# Sensors.net
KiCad netlist of a schematic drawn in Altium Designer
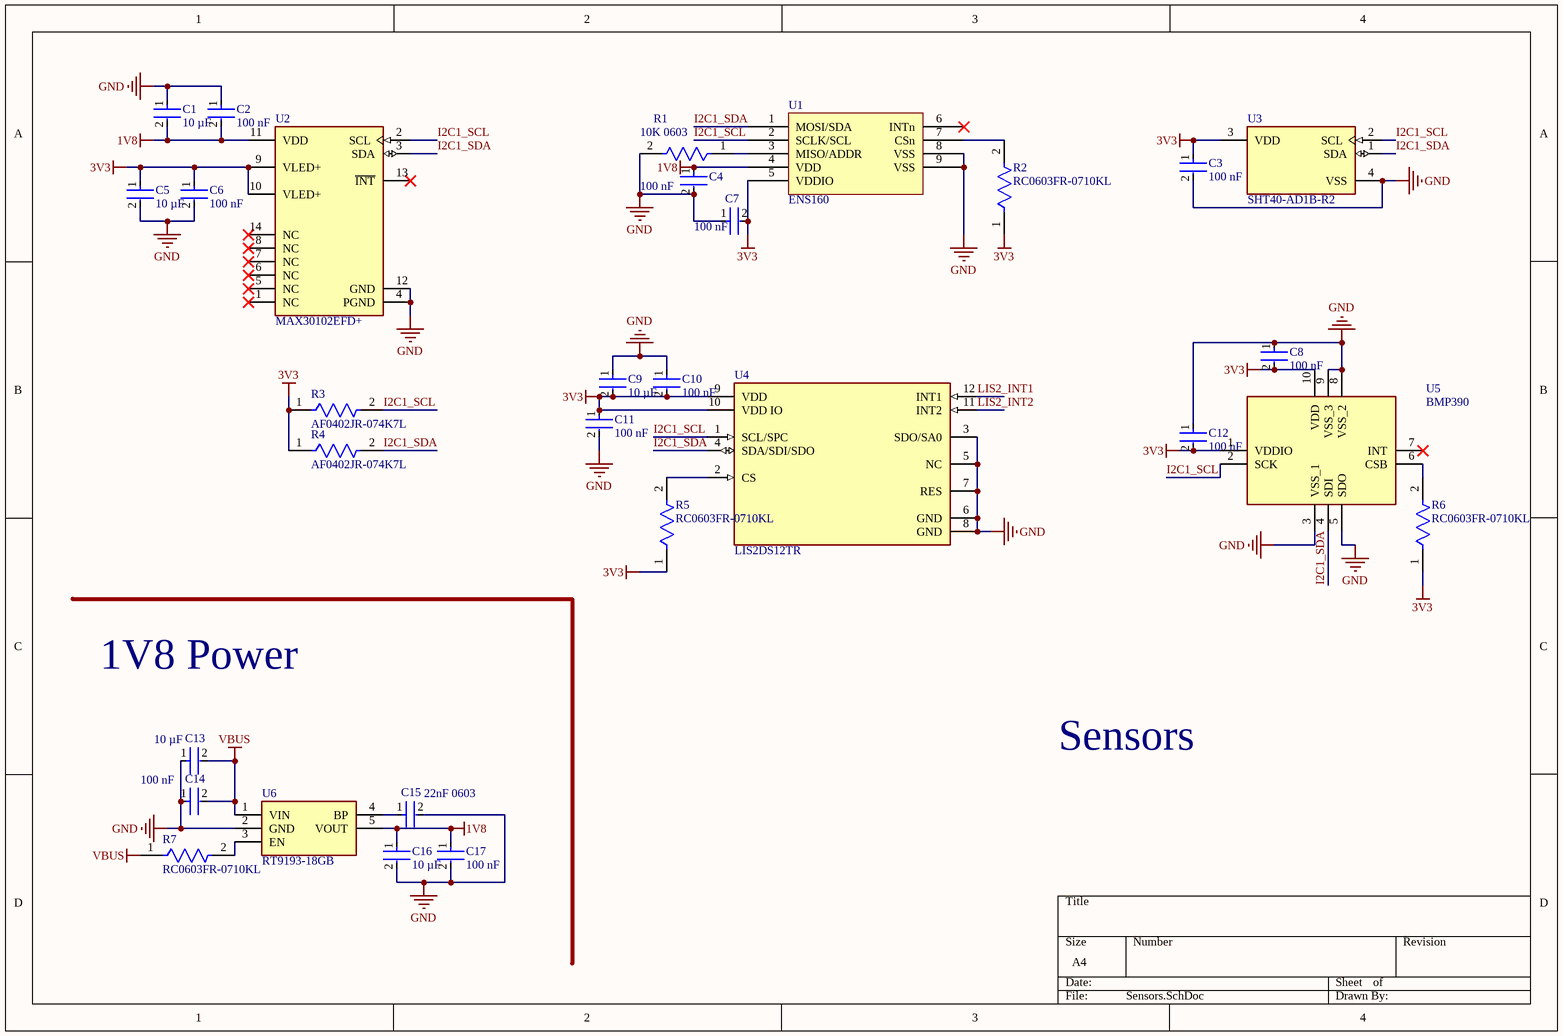
[diagram p0: Sensors.SchDoc]

(export (version "E")
  (design (tool "Eeschema 10.0.6"))
  (components
    (comp (ref "C1")
      (value "10 µF")
      (footprint "FP-CL10-IPC_C")
      (description "Cap Ceramic 10uF 25V X5R ±20% Pad SMD 0603 +85°C T/R")
      (fields (field (name "TOLERANCE") "20%"))
      (libsource (lib "Altium Content Vault") (part "b4654b650e69147ec39a6b967a45e02"))
    )
    (comp (ref "C2")
      (value "100 nF")
      (footprint "FP-CL10-IPC_A")
      (description "Cap Ceramic 100nF 100V X7R ±10% Pad SMD 0603 +125°C T/R")
      (fields (field (name "TOLERANCE") "10%"))
      (libsource (lib "Altium Content Vault") (part "b4654b650e69147ec39a6b967a45e02"))
    )
    (comp (ref "C3")
      (value "100 nF")
      (footprint "FP-CL10-IPC_A")
      (description "Cap Ceramic 100nF 100V X7R ±10% Pad SMD 0603 +125°C T/R")
      (fields (field (name "TOLERANCE") "10%"))
      (libsource (lib "Altium Content Vault") (part "b4654b650e69147ec39a6b967a45e02"))
    )
    (comp (ref "C4")
      (value "100 nF")
      (footprint "FP-CL10-IPC_A")
      (description "Cap Ceramic 100nF 100V X7R ±10% Pad SMD 0603 +125°C T/R")
      (fields (field (name "TOLERANCE") "10%"))
      (libsource (lib "Altium Content Vault") (part "b4654b650e69147ec39a6b967a45e02"))
    )
    (comp (ref "C5")
      (value "10 µF")
      (footprint "FP-CL10-IPC_C")
      (description "Cap Ceramic 10uF 25V X5R ±20% Pad SMD 0603 +85°C T/R")
      (fields (field (name "TOLERANCE") "20%"))
      (libsource (lib "Altium Content Vault") (part "b4654b650e69147ec39a6b967a45e02"))
    )
    (comp (ref "C6")
      (value "100 nF")
      (footprint "FP-CL10-IPC_A")
      (description "Cap Ceramic 100nF 100V X7R ±10% Pad SMD 0603 +125°C T/R")
      (fields (field (name "TOLERANCE") "10%"))
      (libsource (lib "Altium Content Vault") (part "b4654b650e69147ec39a6b967a45e02"))
    )
    (comp (ref "C7")
      (value "100 nF")
      (footprint "FP-CL10-IPC_A")
      (description "Cap Ceramic 100nF 100V X7R ±10% Pad SMD 0603 +125°C T/R")
      (fields (field (name "TOLERANCE") "10%"))
      (libsource (lib "Altium Content Vault") (part "b4654b650e69147ec39a6b967a45e02"))
    )
    (comp (ref "C8")
      (value "100 nF")
      (footprint "FP-CL10-IPC_A")
      (description "Cap Ceramic 100nF 100V X7R ±10% Pad SMD 0603 +125°C T/R")
      (fields (field (name "TOLERANCE") "10%"))
      (libsource (lib "Altium Content Vault") (part "b4654b650e69147ec39a6b967a45e02"))
    )
    (comp (ref "C9")
      (value "10 µF")
      (footprint "FP-CL10-IPC_C")
      (description "Cap Ceramic 10uF 25V X5R ±20% Pad SMD 0603 +85°C T/R")
      (fields (field (name "TOLERANCE") "20%"))
      (libsource (lib "Altium Content Vault") (part "b4654b650e69147ec39a6b967a45e02"))
    )
    (comp (ref "C10")
      (value "100 nF")
      (footprint "FP-CL10-IPC_A")
      (description "Cap Ceramic 100nF 100V X7R ±10% Pad SMD 0603 +125°C T/R")
      (fields (field (name "TOLERANCE") "10%"))
      (libsource (lib "Altium Content Vault") (part "b4654b650e69147ec39a6b967a45e02"))
    )
    (comp (ref "C11")
      (value "100 nF")
      (footprint "FP-CL10-IPC_A")
      (description "Cap Ceramic 100nF 100V X7R ±10% Pad SMD 0603 +125°C T/R")
      (fields (field (name "TOLERANCE") "10%"))
      (libsource (lib "Altium Content Vault") (part "b4654b650e69147ec39a6b967a45e02"))
    )
    (comp (ref "C12")
      (value "100 nF")
      (footprint "FP-CL10-IPC_A")
      (description "Cap Ceramic 100nF 100V X7R ±10% Pad SMD 0603 +125°C T/R")
      (fields (field (name "TOLERANCE") "10%"))
      (libsource (lib "Altium Content Vault") (part "b4654b650e69147ec39a6b967a45e02"))
    )
    (comp (ref "C13")
      (value "10 µF")
      (footprint "FP-CL10-IPC_C")
      (description "Cap Ceramic 10uF 25V X5R ±20% Pad SMD 0603 +85°C T/R")
      (fields (field (name "TOLERANCE") "20%"))
      (libsource (lib "Altium Content Vault") (part "b4654b650e69147ec39a6b967a45e02"))
    )
    (comp (ref "C14")
      (value "100 nF")
      (footprint "FP-CL10-IPC_A")
      (description "Cap Ceramic 100nF 100V X7R ±10% Pad SMD 0603 +125°C T/R")
      (fields (field (name "TOLERANCE") "10%"))
      (libsource (lib "Altium Content Vault") (part "b4654b650e69147ec39a6b967a45e02"))
    )
    (comp (ref "C15")
      (value "22nF 0603")
      (footprint "FP-0603-L_1_6_0_15-W_0_81-IPC_C")
      (description "General Purpose Ceramic Capacitor, 0603, 22nF, 10%, X7R, 15%, 25V")
      (fields (field (name "TOLERANCE") "10%") (field (name "VOLTAGE") "25V"))
      (libsource (lib "Altium Content Vault") (part "02cd4be3c70576c341d710602a673aa"))
    )
    (comp (ref "C16")
      (value "10 µF")
      (footprint "FP-CL10-IPC_C")
      (description "Cap Ceramic 10uF 25V X5R ±20% Pad SMD 0603 +85°C T/R")
      (fields (field (name "TOLERANCE") "20%"))
      (libsource (lib "Altium Content Vault") (part "b4654b650e69147ec39a6b967a45e02"))
    )
    (comp (ref "C17")
      (value "100 nF")
      (footprint "FP-CL10-IPC_A")
      (description "Cap Ceramic 100nF 100V X7R ±10% Pad SMD 0603 +125°C T/R")
      (fields (field (name "TOLERANCE") "10%"))
      (libsource (lib "Altium Content Vault") (part "b4654b650e69147ec39a6b967a45e02"))
    )
    (comp (ref "R1")
      (value "10K 0603")
      (footprint "FP-RC0603-0_55-IPC_C")
      (description "RES 10K OHM 1% 1/10W 0603")
      (fields (field (name "TOLERANCE") "1%"))
      (libsource (lib "Altium Content Vault") (part "1029c3af85768c4190bb7ad29bc67b5"))
    )
    (comp (ref "R2")
      (value "RC0603FR-0710KL")
      (footprint "FP-RC0603-0_55-IPC_C")
      (description "RES 10K OHM 1% 1/10W 0603")
      (fields (field (name "TOLERANCE") "1%"))
      (libsource (lib "Altium Content Vault") (part "1029c3af85768c4190bb7ad29bc67b5"))
    )
    (comp (ref "R3")
      (value "AF0402JR-074K7L")
      (footprint "FP-AF0402-IPC_B")
      (description "Anti-Sulfurated Chip Resistors Automotive Grade 4.7kΩ 5% 100ppm/°C 0402")
      (fields (field (name "TOLERANCE") "5%"))
      (libsource (lib "Altium Content Vault") (part "1029c3af85768c4190bb7ad29bc67b5"))
    )
    (comp (ref "R4")
      (value "AF0402JR-074K7L")
      (footprint "FP-AF0402-IPC_B")
      (description "Anti-Sulfurated Chip Resistors Automotive Grade 4.7kΩ 5% 100ppm/°C 0402")
      (fields (field (name "TOLERANCE") "5%"))
      (libsource (lib "Altium Content Vault") (part "1029c3af85768c4190bb7ad29bc67b5"))
    )
    (comp (ref "R5")
      (value "RC0603FR-0710KL")
      (footprint "FP-RC0603-0_55-IPC_C")
      (description "RES 10K OHM 1% 1/10W 0603")
      (fields (field (name "TOLERANCE") "1%"))
      (libsource (lib "Altium Content Vault") (part "1029c3af85768c4190bb7ad29bc67b5"))
    )
    (comp (ref "R6")
      (value "RC0603FR-0710KL")
      (footprint "FP-RC0603-0_55-IPC_C")
      (description "RES 10K OHM 1% 1/10W 0603")
      (fields (field (name "TOLERANCE") "1%"))
      (libsource (lib "Altium Content Vault") (part "1029c3af85768c4190bb7ad29bc67b5"))
    )
    (comp (ref "R7")
      (value "RC0603FR-0710KL")
      (footprint "FP-RC0603-0_55-IPC_C")
      (description "RES 10K OHM 1% 1/10W 0603")
      (fields (field (name "TOLERANCE") "1%"))
      (libsource (lib "Altium Content Vault") (part "1029c3af85768c4190bb7ad29bc67b5"))
    )
    (comp (ref "U1") (value "ENS160") (footprint "ENS_160") (libsource (lib "Demo") (part "ENS160")))
    (comp (ref "U2")
      (value "MAX30102EFD+")
      (footprint "FP-F143A5-1-MFG")
      (description "IC SENSOR OXIMETER/HEARTRATE")
      (fields
        (field (name "MANUFACTURER") "Maxim Integrated")
        (field (name "OCTOPART") "https://octopart.com/max30102efd%2B-maxim+integrated-59568799")
      )
      (libsource (lib "Altium Content Vault") (part "5fad416c1761f996ad02d0b395f9532"))
    )
    (comp (ref "U3")
      (value "SHT40-AD1B-R2")
      (footprint "FP-SHT40-AD1B-R2-MFG")
      (description "SENSOR HUMIDITY 100 RH SMD")
      (libsource (lib "Altium Content Vault") (part "985d6b895d3abb4f56b1b691ea450a8"))
    )
    (comp (ref "U4")
      (value "LIS2DS12TR")
      (footprint "FP-LGA12_8566956-MFG")
      (description "ACCEL 2-16G I2C/SPI 12LGA")
      (libsource (lib "Altium Content Vault") (part "71777070b7db0ed8ebb1a0f678b9644"))
    )
    (comp (ref "U5")
      (value "BMP390")
      (footprint "BMP390")
      (description "Board Mount Pressure Sensors")
      (libsource (lib "Demo") (part "BMP390"))
    )
    (comp (ref "U6")
      (value "RT9193-18GB")
      (footprint "SOT94P279X130-5N")
      (description "IC REG LINEAR 1.8V 300MA SOT23-5")
      (libsource (lib "Demo") (part "RT9193-18GB"))
    )
  )
  (nets
    (net (code "1") (name "/I2C1_SCL") (class "Default")
      (node (ref "R3") (pin "2") (pinfunction "2_2") (pintype "passive"))
      (node (ref "U1") (pin "2") (pinfunction "SCLK/SCL_2") (pintype "passive"))
      (node (ref "U2") (pin "2") (pinfunction "SCL_2") (pintype "input"))
      (node (ref "U3") (pin "2") (pinfunction "SCL_2") (pintype "input"))
      (node (ref "U4") (pin "1") (pinfunction "SCL/SPC_1") (pintype "input"))
      (node (ref "U5") (pin "2") (pinfunction "SCK_2") (pintype "passive"))
    )
    (net (code "2") (name "/I2C1_SDA") (class "Default")
      (node (ref "R4") (pin "2") (pinfunction "2_2") (pintype "passive"))
      (node (ref "U1") (pin "1") (pinfunction "MOSI/SDA_1") (pintype "passive"))
      (node (ref "U2") (pin "3") (pinfunction "SDA_3") (pintype "bidirectional"))
      (node (ref "U3") (pin "1") (pinfunction "SDA_1") (pintype "bidirectional"))
      (node (ref "U4") (pin "4") (pinfunction "SDA/SDI/SDO_4") (pintype "bidirectional"))
      (node (ref "U5") (pin "4") (pinfunction "SDI_4") (pintype "passive"))
    )
    (net (code "3") (name "/LIS2_INT1") (class "Default")
      (node (ref "U4") (pin "12") (pinfunction "INT1_12") (pintype "input"))
    )
    (net (code "4") (name "/LIS2_INT2") (class "Default")
      (node (ref "U4") (pin "11") (pinfunction "INT2_11") (pintype "input"))
    )
    (net (code "5") (name "1V8") (class "Default")
      (node (ref "C1") (pin "2") (pinfunction "2_2") (pintype "passive"))
      (node (ref "C16") (pin "1") (pinfunction "1_1") (pintype "passive"))
      (node (ref "C17") (pin "1") (pinfunction "1_1") (pintype "passive"))
      (node (ref "C2") (pin "2") (pinfunction "2_2") (pintype "passive"))
      (node (ref "C4") (pin "1") (pinfunction "1_1") (pintype "passive"))
      (node (ref "U1") (pin "4") (pinfunction "VDD_4") (pintype "power_in"))
      (node (ref "U2") (pin "11") (pinfunction "VDD_11") (pintype "power_in"))
      (node (ref "U6") (pin "5") (pinfunction "VOUT_5") (pintype "passive"))
    )
    (net (code "6") (name "3V3") (class "Default")
      (node (ref "C10") (pin "2") (pinfunction "2_2") (pintype "passive"))
      (node (ref "C11") (pin "1") (pinfunction "1_1") (pintype "passive"))
      (node (ref "C12") (pin "2") (pinfunction "2_2") (pintype "passive"))
      (node (ref "C3") (pin "1") (pinfunction "1_1") (pintype "passive"))
      (node (ref "C5") (pin "1") (pinfunction "1_1") (pintype "passive"))
      (node (ref "C6") (pin "1") (pinfunction "1_1") (pintype "passive"))
      (node (ref "C7") (pin "2") (pinfunction "2_2") (pintype "passive"))
      (node (ref "C8") (pin "2") (pinfunction "2_2") (pintype "passive"))
      (node (ref "C9") (pin "2") (pinfunction "2_2") (pintype "passive"))
      (node (ref "R2") (pin "1") (pinfunction "1_1") (pintype "passive"))
      (node (ref "R3") (pin "1") (pinfunction "1_1") (pintype "passive"))
      (node (ref "R4") (pin "1") (pinfunction "1_1") (pintype "passive"))
      (node (ref "R5") (pin "1") (pinfunction "1_1") (pintype "passive"))
      (node (ref "R6") (pin "1") (pinfunction "1_1") (pintype "passive"))
      (node (ref "U1") (pin "5") (pinfunction "VDDIO_5") (pintype "power_in"))
      (node (ref "U2") (pin "10") (pinfunction "VLED+_10") (pintype "power_in"))
      (node (ref "U2") (pin "9") (pinfunction "VLED+_9") (pintype "power_in"))
      (node (ref "U3") (pin "3") (pinfunction "VDD_3") (pintype "power_in"))
      (node (ref "U4") (pin "10") (pinfunction "VDD_IO_10") (pintype "power_in"))
      (node (ref "U4") (pin "9") (pinfunction "VDD_9") (pintype "power_in"))
      (node (ref "U5") (pin "1") (pinfunction "VDDIO_1") (pintype "power_in"))
      (node (ref "U5") (pin "10") (pinfunction "VDD_10") (pintype "power_in"))
    )
    (net (code "7") (name "GND") (class "Default")
      (node (ref "C1") (pin "1") (pinfunction "1_1") (pintype "passive"))
      (node (ref "C10") (pin "1") (pinfunction "1_1") (pintype "passive"))
      (node (ref "C11") (pin "2") (pinfunction "2_2") (pintype "passive"))
      (node (ref "C12") (pin "1") (pinfunction "1_1") (pintype "passive"))
      (node (ref "C13") (pin "1") (pinfunction "1_1") (pintype "passive"))
      (node (ref "C14") (pin "1") (pinfunction "1_1") (pintype "passive"))
      (node (ref "C15") (pin "2") (pinfunction "2_2") (pintype "passive"))
      (node (ref "C16") (pin "2") (pinfunction "2_2") (pintype "passive"))
      (node (ref "C17") (pin "2") (pinfunction "2_2") (pintype "passive"))
      (node (ref "C2") (pin "1") (pinfunction "1_1") (pintype "passive"))
      (node (ref "C3") (pin "2") (pinfunction "2_2") (pintype "passive"))
      (node (ref "C4") (pin "2") (pinfunction "2_2") (pintype "passive"))
      (node (ref "C5") (pin "2") (pinfunction "2_2") (pintype "passive"))
      (node (ref "C6") (pin "2") (pinfunction "2_2") (pintype "passive"))
      (node (ref "C7") (pin "1") (pinfunction "1_1") (pintype "passive"))
      (node (ref "C8") (pin "1") (pinfunction "1_1") (pintype "passive"))
      (node (ref "C9") (pin "1") (pinfunction "1_1") (pintype "passive"))
      (node (ref "R1") (pin "2") (pinfunction "2_2") (pintype "passive"))
      (node (ref "U1") (pin "8") (pinfunction "VSS_8") (pintype "power_in"))
      (node (ref "U1") (pin "9") (pinfunction "VSS_9") (pintype "power_in"))
      (node (ref "U2") (pin "12") (pinfunction "GND_12") (pintype "power_in"))
      (node (ref "U2") (pin "4") (pinfunction "PGND_4") (pintype "power_in"))
      (node (ref "U3") (pin "4") (pinfunction "VSS_4") (pintype "power_in"))
      (node (ref "U4") (pin "3") (pinfunction "SDO/SA0_3") (pintype "passive"))
      (node (ref "U4") (pin "5") (pinfunction "NC_5") (pintype "passive"))
      (node (ref "U4") (pin "6") (pinfunction "GND_6") (pintype "power_in"))
      (node (ref "U4") (pin "7") (pinfunction "RES_7") (pintype "power_in"))
      (node (ref "U4") (pin "8") (pinfunction "GND_8") (pintype "power_in"))
      (node (ref "U5") (pin "3") (pinfunction "VSS_1_3") (pintype "power_in"))
      (node (ref "U5") (pin "5") (pinfunction "SDO_5") (pintype "passive"))
      (node (ref "U5") (pin "8") (pinfunction "VSS_2_8") (pintype "power_in"))
      (node (ref "U5") (pin "9") (pinfunction "VSS_3_9") (pintype "power_in"))
      (node (ref "U6") (pin "2") (pinfunction "GND_2") (pintype "passive"))
    )
    (net (code "8") (name "Net-(U1-CSn)") (class "Default")
      (node (ref "R2") (pin "2") (pinfunction "2_2") (pintype "passive"))
      (node (ref "U1") (pin "7") (pinfunction "CSn_7") (pintype "passive"))
    )
    (net (code "9") (name "Net-(U1-MISO{slash}ADDR)") (class "Default")
      (node (ref "R1") (pin "1") (pinfunction "1_1") (pintype "passive"))
      (node (ref "U1") (pin "3") (pinfunction "MISO/ADDR_3") (pintype "passive"))
    )
    (net (code "10") (name "Net-(U4-CS)") (class "Default")
      (node (ref "R5") (pin "2") (pinfunction "2_2") (pintype "passive"))
      (node (ref "U4") (pin "2") (pinfunction "CS_2") (pintype "input"))
    )
    (net (code "11") (name "Net-(U5-CSB)") (class "Default")
      (node (ref "R6") (pin "2") (pinfunction "2_2") (pintype "passive"))
      (node (ref "U5") (pin "6") (pinfunction "CSB_6") (pintype "passive"))
    )
    (net (code "12") (name "Net-(U6-BP)") (class "Default")
      (node (ref "C15") (pin "1") (pinfunction "1_1") (pintype "passive"))
      (node (ref "U6") (pin "4") (pinfunction "BP_4") (pintype "passive"))
    )
    (net (code "13") (name "Net-(U6-EN)") (class "Default")
      (node (ref "R7") (pin "2") (pinfunction "2_2") (pintype "passive"))
      (node (ref "U6") (pin "3") (pinfunction "EN_3") (pintype "passive"))
    )
    (net (code "14") (name "VBUS") (class "Default")
      (node (ref "C13") (pin "2") (pinfunction "2_2") (pintype "passive"))
      (node (ref "C14") (pin "2") (pinfunction "2_2") (pintype "passive"))
      (node (ref "R7") (pin "1") (pinfunction "1_1") (pintype "passive"))
      (node (ref "U6") (pin "1") (pinfunction "VIN_1") (pintype "passive"))
    )
    (net (code "15") (name "unconnected-(U1-INTn-Pad6)") (class "Default")
      (node (ref "U1") (pin "6") (pinfunction "INTn_6") (pintype "passive+no_connect"))
    )
    (net (code "16") (name "unconnected-(U2-NC-Pad1)") (class "Default")
      (node (ref "U2") (pin "1") (pinfunction "NC_1") (pintype "passive+no_connect"))
    )
    (net (code "17") (name "unconnected-(U2-NC-Pad5)") (class "Default")
      (node (ref "U2") (pin "5") (pinfunction "NC_5") (pintype "passive+no_connect"))
    )
    (net (code "18") (name "unconnected-(U2-NC-Pad6)") (class "Default")
      (node (ref "U2") (pin "6") (pinfunction "NC_6") (pintype "passive+no_connect"))
    )
    (net (code "19") (name "unconnected-(U2-NC-Pad7)") (class "Default")
      (node (ref "U2") (pin "7") (pinfunction "NC_7") (pintype "passive+no_connect"))
    )
    (net (code "20") (name "unconnected-(U2-NC-Pad8)") (class "Default")
      (node (ref "U2") (pin "8") (pinfunction "NC_8") (pintype "passive+no_connect"))
    )
    (net (code "21") (name "unconnected-(U2-NC-Pad14)") (class "Default")
      (node (ref "U2") (pin "14") (pinfunction "NC_14") (pintype "passive+no_connect"))
    )
    (net (code "22") (name "unconnected-(U2-~{INT}-Pad13)") (class "Default")
      (node (ref "U2") (pin "13") (pinfunction "~{INT}_13") (pintype "open_collector+no_connect"))
    )
    (net (code "23") (name "unconnected-(U5-INT-Pad7)") (class "Default")
      (node (ref "U5") (pin "7") (pinfunction "INT_7") (pintype "passive+no_connect"))
    )
  )
)
